# IsoSupply.net
KiCad netlist of a schematic drawn in Altium Designer
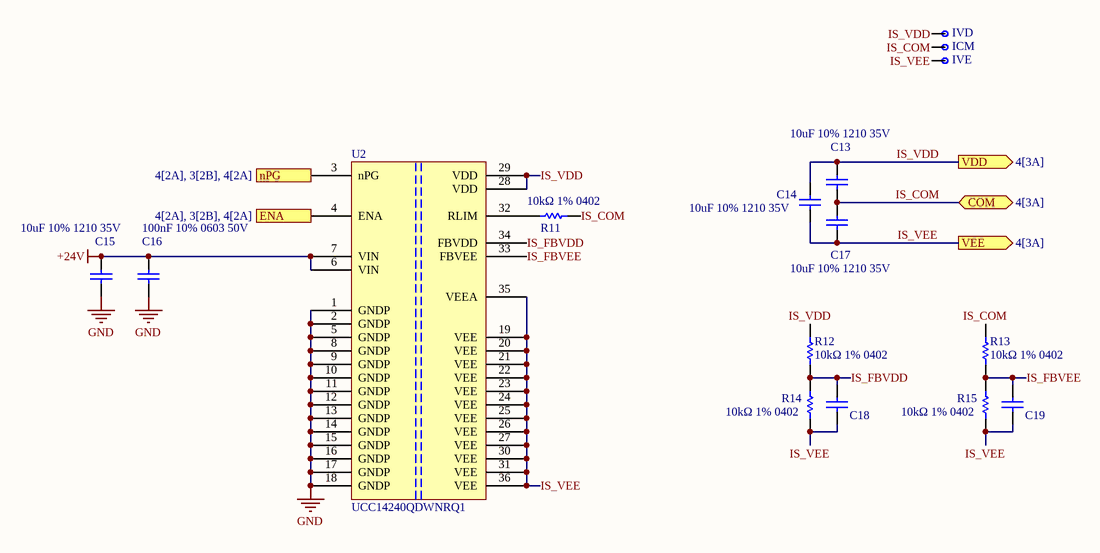
[diagram p0: IsoSupply.SchDoc]

(export (version "E")
  (design (tool "Eeschema 10.0.6"))
  (components
    (comp (ref "C13")
      (value "10uF 10% 1210 35V")
      (footprint "1210N")
      (fields (field (name "TOLERANCE") "10") (field (name "VOLTAGE") "35"))
      (libsource (lib "MiscPassives") (part "C1210"))
    )
    (comp (ref "C14")
      (value "10uF 10% 1210 35V")
      (footprint "1210N")
      (fields (field (name "TOLERANCE") "10") (field (name "VOLTAGE") "35"))
      (libsource (lib "MiscPassives") (part "C1210"))
    )
    (comp (ref "C15")
      (value "10uF 10% 1210 35V")
      (footprint "1210N")
      (fields (field (name "TOLERANCE") "10") (field (name "VOLTAGE") "35"))
      (libsource (lib "MiscPassives") (part "C1210"))
    )
    (comp (ref "C16")
      (value "100nF 10% 0603 50V")
      (footprint "0603N")
      (fields (field (name "TOLERANCE") "10") (field (name "VOLTAGE") "50"))
      (libsource (lib "MiscPassives") (part "C0603"))
    )
    (comp (ref "C17")
      (value "10uF 10% 1210 35V")
      (footprint "1210N")
      (fields (field (name "TOLERANCE") "10") (field (name "VOLTAGE") "35"))
      (libsource (lib "MiscPassives") (part "C1210"))
    )
    (comp (ref "C18")
      (value "100nF 10% 0402 25V")
      (footprint "0402N")
      (fields (field (name "TOLERANCE") "10") (field (name "VOLTAGE") "25"))
      (libsource (lib "MiscPassives") (part "C0402"))
    )
    (comp (ref "C19")
      (value "100nF 10% 0402 25V")
      (footprint "0402N")
      (fields (field (name "TOLERANCE") "10") (field (name "VOLTAGE") "25"))
      (libsource (lib "MiscPassives") (part "C0402"))
    )
    (comp (ref "ICM")
      (value "Testpoint")
      (footprint "Testpoint-Footprint-1")
      (libsource (lib "Saule S.A") (part "Testpoint"))
    )
    (comp (ref "IVD")
      (value "Testpoint")
      (footprint "Testpoint-Footprint-1")
      (libsource (lib "Saule S.A") (part "Testpoint"))
    )
    (comp (ref "IVE")
      (value "Testpoint")
      (footprint "Testpoint-Footprint-1")
      (libsource (lib "Saule S.A") (part "Testpoint"))
    )
    (comp (ref "R11")
      (value "10kΩ 1% 0402")
      (footprint "0402N")
      (fields (field (name "TOLERANCE") "1"))
      (libsource (lib "MiscPassives") (part "R0402"))
    )
    (comp (ref "R12")
      (value "10kΩ 1% 0402")
      (footprint "0402N")
      (fields (field (name "TOLERANCE") "1"))
      (libsource (lib "MiscPassives") (part "R0402"))
    )
    (comp (ref "R13")
      (value "10kΩ 1% 0402")
      (footprint "0402N")
      (fields (field (name "TOLERANCE") "1"))
      (libsource (lib "MiscPassives") (part "R0402"))
    )
    (comp (ref "R14")
      (value "10kΩ 1% 0402")
      (footprint "0402N")
      (fields (field (name "TOLERANCE") "1"))
      (libsource (lib "MiscPassives") (part "R0402"))
    )
    (comp (ref "R15")
      (value "10kΩ 1% 0402")
      (footprint "0402N")
      (fields (field (name "TOLERANCE") "1"))
      (libsource (lib "MiscPassives") (part "R0402"))
    )
    (comp (ref "U2")
      (value "UCC14240QDWNRQ1")
      (footprint "UCC14240QDWNRQ1-Footprint-1")
      (libsource (lib "Saule S.A") (part "UCC14240QDWNRQ1-Symbol-1"))
    )
  )
  (nets
    (net (code "1") (name "+24V") (class "Default")
      (node (ref "C15") (pin "2") (pinfunction "2_2") (pintype "passive"))
      (node (ref "C16") (pin "2") (pinfunction "2_2") (pintype "passive"))
      (node (ref "U2") (pin "6") (pinfunction "VIN_6") (pintype "passive"))
      (node (ref "U2") (pin "7") (pinfunction "VIN_7") (pintype "passive"))
    )
    (net (code "2") (name "/ENA") (class "Default")
      (node (ref "U2") (pin "4") (pinfunction "ENA_4") (pintype "passive"))
    )
    (net (code "3") (name "/IS_COM") (class "Default")
      (node (ref "C13") (pin "1") (pinfunction "1_1") (pintype "passive"))
      (node (ref "C17") (pin "2") (pinfunction "2_2") (pintype "passive"))
      (node (ref "ICM") (pin "1") (pinfunction "1_1") (pintype "passive"))
      (node (ref "R11") (pin "1") (pinfunction "1_1") (pintype "passive"))
      (node (ref "R13") (pin "1") (pinfunction "1_1") (pintype "passive"))
    )
    (net (code "4") (name "/IS_FBVDD") (class "Default")
      (node (ref "C18") (pin "1") (pinfunction "1_1") (pintype "passive"))
      (node (ref "R12") (pin "2") (pinfunction "2_2") (pintype "passive"))
      (node (ref "R14") (pin "2") (pinfunction "2_2") (pintype "passive"))
      (node (ref "U2") (pin "34") (pinfunction "FBVDD_34") (pintype "passive"))
    )
    (net (code "5") (name "/IS_FBVEE") (class "Default")
      (node (ref "C19") (pin "1") (pinfunction "1_1") (pintype "passive"))
      (node (ref "R13") (pin "2") (pinfunction "2_2") (pintype "passive"))
      (node (ref "R15") (pin "2") (pinfunction "2_2") (pintype "passive"))
      (node (ref "U2") (pin "33") (pinfunction "FBVEE_33") (pintype "passive"))
    )
    (net (code "6") (name "/IS_VDD") (class "Default")
      (node (ref "C13") (pin "2") (pinfunction "2_2") (pintype "passive"))
      (node (ref "C14") (pin "2") (pinfunction "2_2") (pintype "passive"))
      (node (ref "IVD") (pin "1") (pinfunction "1_1") (pintype "passive"))
      (node (ref "R12") (pin "1") (pinfunction "1_1") (pintype "passive"))
      (node (ref "U2") (pin "28") (pinfunction "VDD_28") (pintype "passive"))
      (node (ref "U2") (pin "29") (pinfunction "VDD_29") (pintype "passive"))
    )
    (net (code "7") (name "/IS_VEE") (class "Default")
      (node (ref "C14") (pin "1") (pinfunction "1_1") (pintype "passive"))
      (node (ref "C17") (pin "1") (pinfunction "1_1") (pintype "passive"))
      (node (ref "C18") (pin "2") (pinfunction "2_2") (pintype "passive"))
      (node (ref "C19") (pin "2") (pinfunction "2_2") (pintype "passive"))
      (node (ref "IVE") (pin "1") (pinfunction "1_1") (pintype "passive"))
      (node (ref "R14") (pin "1") (pinfunction "1_1") (pintype "passive"))
      (node (ref "R15") (pin "1") (pinfunction "1_1") (pintype "passive"))
      (node (ref "U2") (pin "19") (pinfunction "VEE_19") (pintype "passive"))
      (node (ref "U2") (pin "20") (pinfunction "VEE_20") (pintype "passive"))
      (node (ref "U2") (pin "21") (pinfunction "VEE_21") (pintype "passive"))
      (node (ref "U2") (pin "22") (pinfunction "VEE_22") (pintype "passive"))
      (node (ref "U2") (pin "23") (pinfunction "VEE_23") (pintype "passive"))
      (node (ref "U2") (pin "24") (pinfunction "VEE_24") (pintype "passive"))
      (node (ref "U2") (pin "25") (pinfunction "VEE_25") (pintype "passive"))
      (node (ref "U2") (pin "26") (pinfunction "VEE_26") (pintype "passive"))
      (node (ref "U2") (pin "27") (pinfunction "VEE_27") (pintype "passive"))
      (node (ref "U2") (pin "30") (pinfunction "VEE_30") (pintype "passive"))
      (node (ref "U2") (pin "31") (pinfunction "VEE_31") (pintype "passive"))
      (node (ref "U2") (pin "35") (pinfunction "VEEA_35") (pintype "passive"))
      (node (ref "U2") (pin "36") (pinfunction "VEE_36") (pintype "passive"))
    )
    (net (code "8") (name "/nPG") (class "Default")
      (node (ref "U2") (pin "3") (pinfunction "nPG_3") (pintype "passive"))
    )
    (net (code "9") (name "GND") (class "Default")
      (node (ref "C15") (pin "1") (pinfunction "1_1") (pintype "passive"))
      (node (ref "C16") (pin "1") (pinfunction "1_1") (pintype "passive"))
      (node (ref "U2") (pin "1") (pinfunction "GNDP_1") (pintype "passive"))
      (node (ref "U2") (pin "10") (pinfunction "GNDP_10") (pintype "passive"))
      (node (ref "U2") (pin "11") (pinfunction "GNDP_11") (pintype "passive"))
      (node (ref "U2") (pin "12") (pinfunction "GNDP_12") (pintype "passive"))
      (node (ref "U2") (pin "13") (pinfunction "GNDP_13") (pintype "passive"))
      (node (ref "U2") (pin "14") (pinfunction "GNDP_14") (pintype "passive"))
      (node (ref "U2") (pin "15") (pinfunction "GNDP_15") (pintype "passive"))
      (node (ref "U2") (pin "16") (pinfunction "GNDP_16") (pintype "passive"))
      (node (ref "U2") (pin "17") (pinfunction "GNDP_17") (pintype "passive"))
      (node (ref "U2") (pin "18") (pinfunction "GNDP_18") (pintype "passive"))
      (node (ref "U2") (pin "2") (pinfunction "GNDP_2") (pintype "passive"))
      (node (ref "U2") (pin "5") (pinfunction "GNDP_5") (pintype "passive"))
      (node (ref "U2") (pin "8") (pinfunction "GNDP_8") (pintype "passive"))
      (node (ref "U2") (pin "9") (pinfunction "GNDP_9") (pintype "passive"))
    )
    (net (code "10") (name "Net-(U2-RLIM)") (class "Default")
      (node (ref "R11") (pin "2") (pinfunction "2_2") (pintype "passive"))
      (node (ref "U2") (pin "32") (pinfunction "RLIM_32") (pintype "passive"))
    )
  )
)
